# IoT_Indoor_Climate_Sensor-_upgraded.net
KiCad netlist of a schematic drawn in EasyEDA
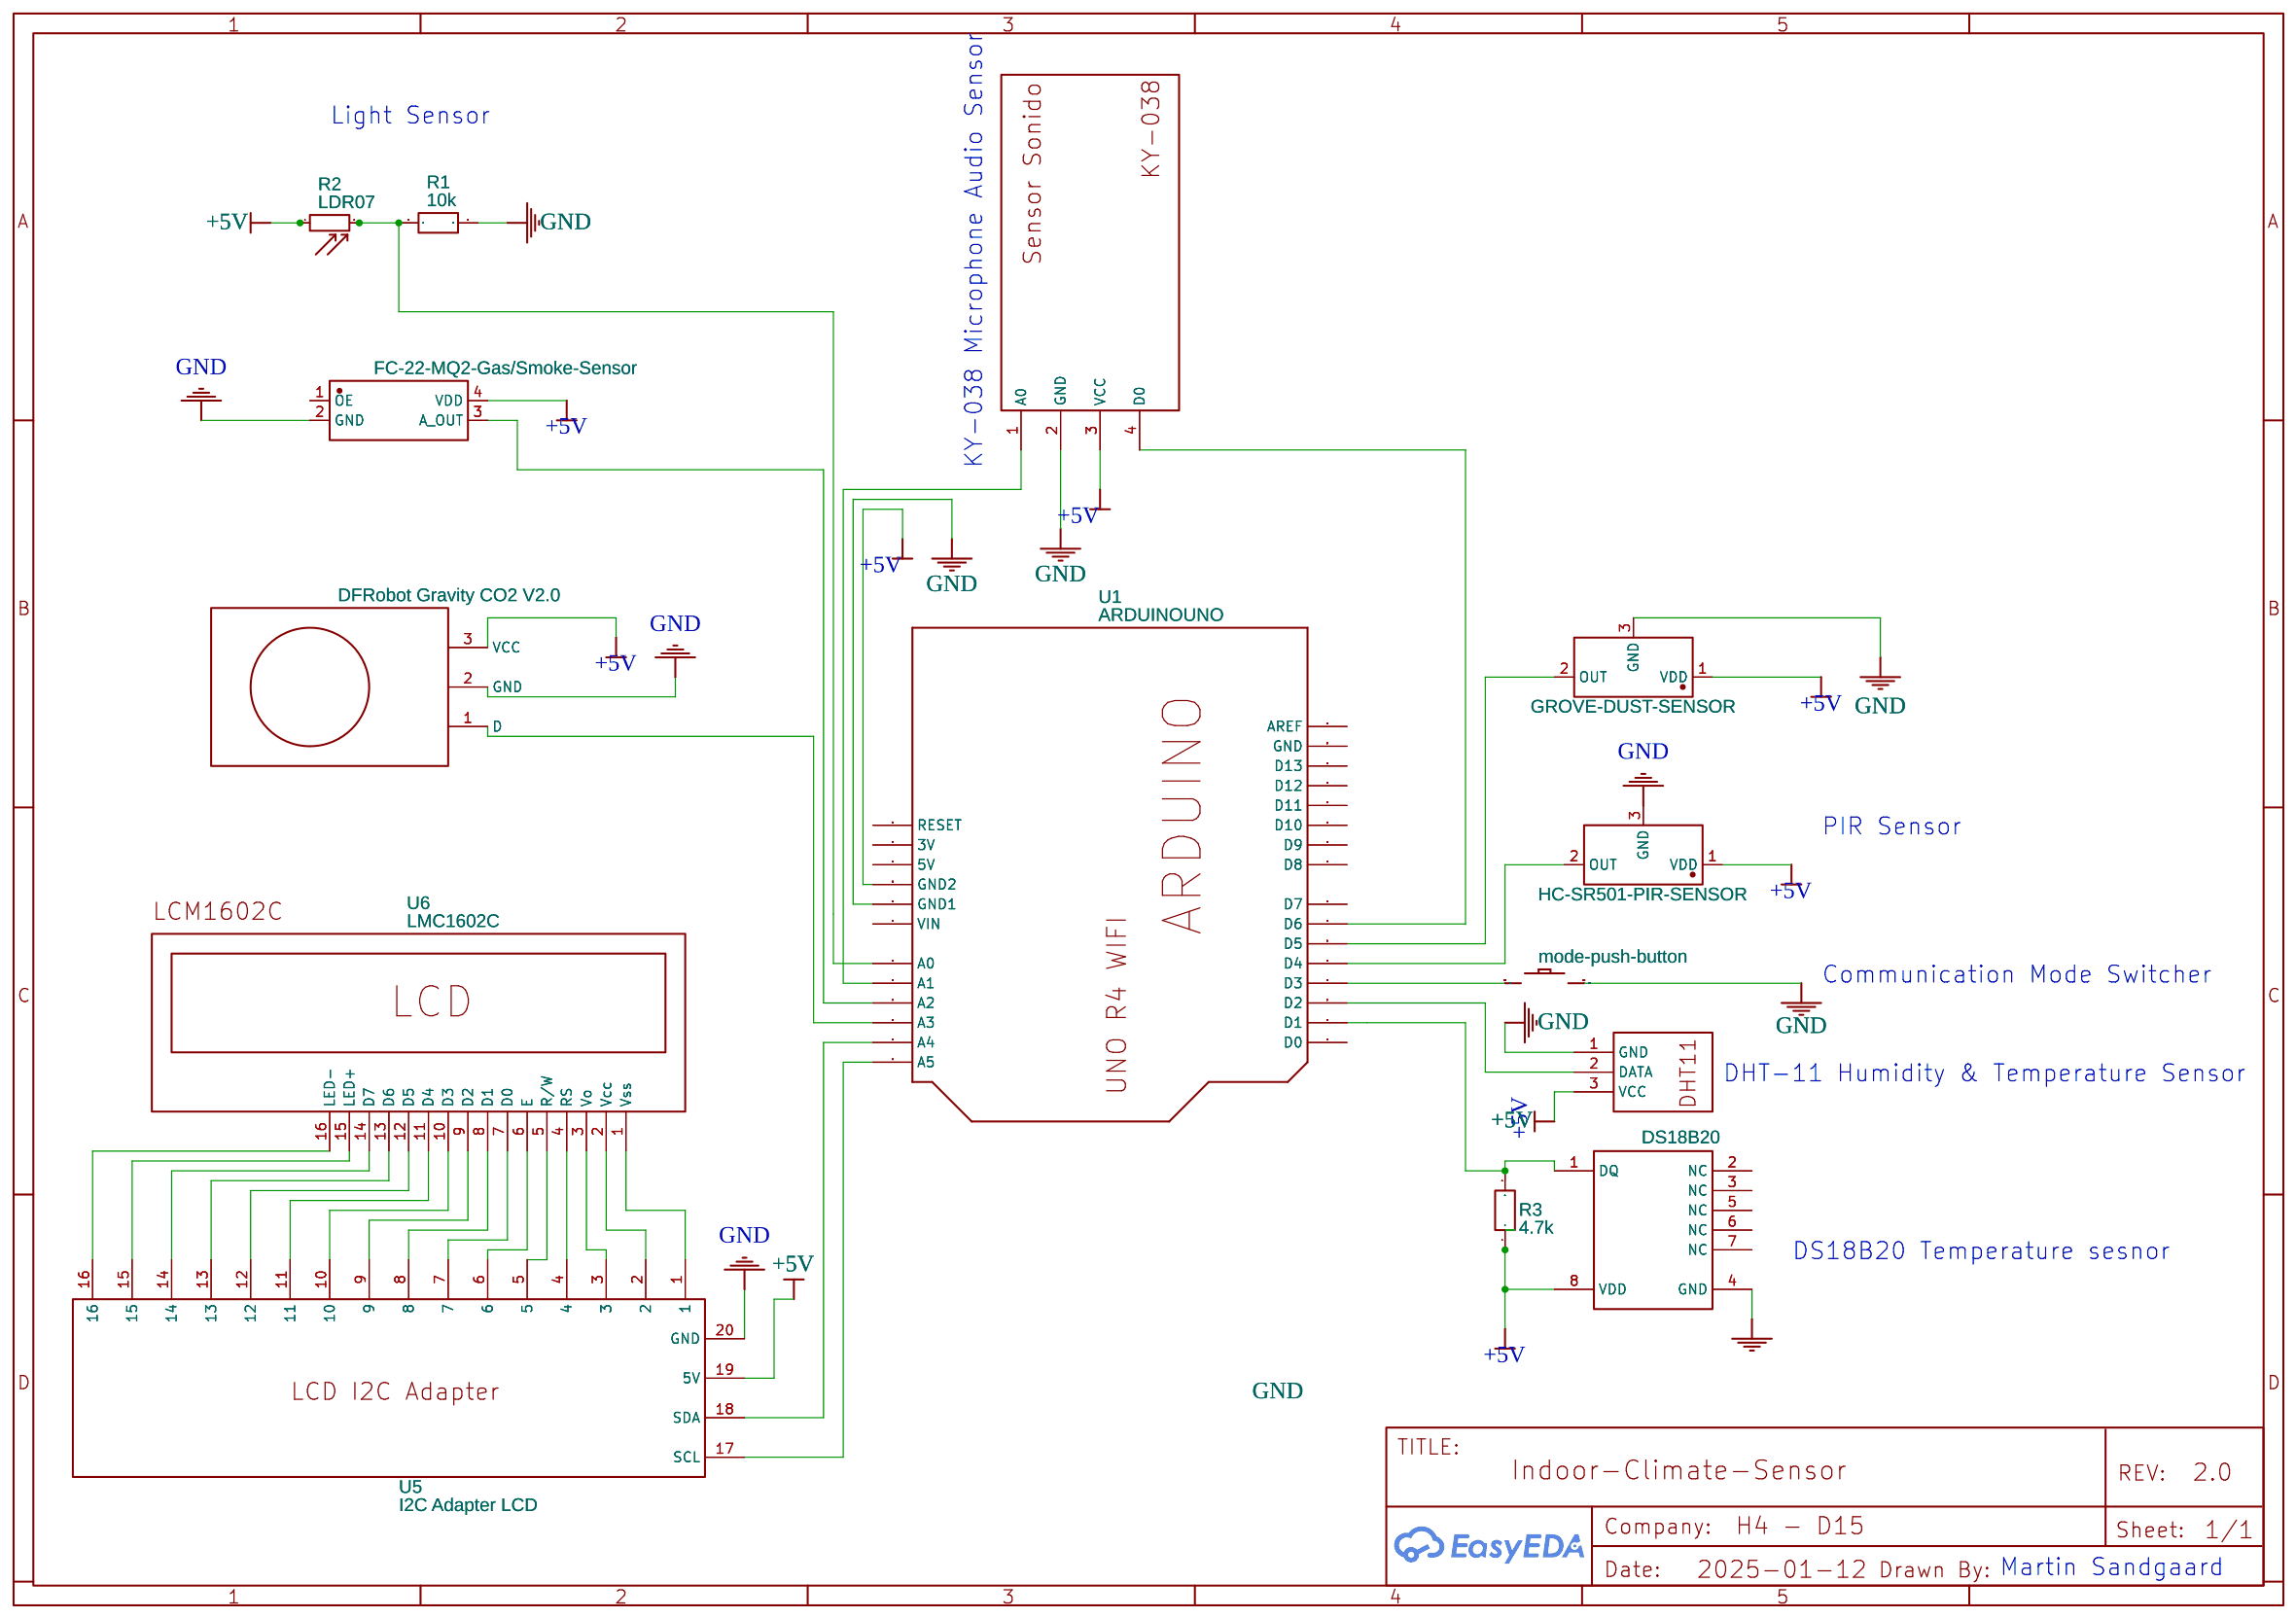
[diagram p0: schematic sheet]

(export (version "E")
  (design (tool "Eeschema 10.0.6"))
  (components
    (comp (ref "1") (value "mode-push-button") (libsource (lib "") (part "button")))
    (comp (ref "GROVE-DUST-SENSOR")
      (value "EKMB1309113K")
      (fields (field (name "Manufacturer") "PANASONIC(松下)"))
      (libsource (lib "") (part "EKMB1309113K"))
    )
    (comp (ref "HC-SR501-PIR-SENSOR")
      (value "EKMB1309113K")
      (fields (field (name "Manufacturer") "PANASONIC(松下)"))
      (libsource (lib "") (part "EKMB1309113K_1"))
    )
    (comp (ref "OSC1")
      (value "FC-22-MQ2-Gas/Smoke-Sensor")
      (fields (field (name "Manufacturer Part") "AMPMDFC-22.0000T3") (field (name "Manufacturer") "ABRACON"))
      (libsource (lib "") (part "AMPMDFC-22.0000T3"))
    )
    (comp (ref "R1") (value "10k") (libsource (lib "") (part "R_0603_EU_1")))
    (comp (ref "R2") (value "LDR07") (libsource (lib "") (part "LDR07")))
    (comp (ref "R3") (value "4.7k") (libsource (lib "") (part "R_0603_EU")))
    (comp (ref "U1") (value "ARDUINOUNO") (libsource (lib "") (part "ARDUINOUNO")))
    (comp (ref "U2") (value "DS18B20") (libsource (lib "") (part "DS18B20U+")))
    (comp (ref "U3")
      (value "KY-038 Microphone Sound Sensor")
      (libsource (lib "") (part "KY-037 KY038 SENSOR SONIDO COPY"))
    )
    (comp (ref "U4") (value "DHT-11") (libsource (lib "") (part "DHT-11")))
    (comp (ref "U5") (value "I2C Adapter LCD") (libsource (lib "") (part "I2C Adapter LCD")))
    (comp (ref "U6") (value "LMC1602C") (libsource (lib "") (part "LMC1602C")))
    (comp (ref "U7")
      (value "DFRobot Gravity CO2 V2.0")
      (libsource (lib "") (part "DFRobot Gravity - czujnik dwutlenku węgla CO2 - elektrochemiczny"))
    )
  )
  (nets
    (net (code "1") (name "+5V") (class "Default")
      (node (ref "GROVE-DUST-SENSOR") (pin "1") (pinfunction "VDD_1") (pintype "unspecified"))
      (node (ref "HC-SR501-PIR-SENSOR") (pin "1") (pinfunction "VDD_1") (pintype "unspecified"))
      (node (ref "OSC1") (pin "4") (pinfunction "VDD_4") (pintype "unspecified"))
      (node (ref "R2") (pin "1") (pintype "unspecified"))
      (node (ref "R3") (pin "1") (pinfunction "1_1") (pintype "unspecified"))
      (node (ref "U1") (pin "GND2") (pinfunction "GND2_GND2") (pintype "passive"))
      (node (ref "U2") (pin "8") (pinfunction "VDD_8") (pintype "passive"))
      (node (ref "U3") (pin "3") (pinfunction "VCC_3") (pintype "unspecified"))
      (node (ref "U4") (pin "3") (pinfunction "VCC_3") (pintype "unspecified"))
      (node (ref "U5") (pin "19") (pinfunction "5V_19") (pintype "unspecified"))
    )
    (net (code "2") (name "GND") (class "Default")
      (node (ref "1") (pin "P$ACTIVE") (pinfunction "P$ACTIVE_P$ACTIVE") (pintype "unspecified"))
      (node (ref "GROVE-DUST-SENSOR") (pin "3") (pinfunction "GND_3") (pintype "unspecified"))
      (node (ref "HC-SR501-PIR-SENSOR") (pin "3") (pinfunction "GND_3") (pintype "unspecified"))
      (node (ref "OSC1") (pin "2") (pinfunction "GND_2") (pintype "unspecified"))
      (node (ref "R1") (pin "1") (pinfunction "1_1") (pintype "unspecified"))
      (node (ref "U1") (pin "GND1") (pinfunction "GND1_GND1") (pintype "passive"))
      (node (ref "U2") (pin "4") (pinfunction "GND_4") (pintype "passive"))
      (node (ref "U3") (pin "2") (pinfunction "GND_2") (pintype "unspecified"))
      (node (ref "U4") (pin "1") (pinfunction "GND_1") (pintype "unspecified"))
      (node (ref "U5") (pin "20") (pinfunction "GND_20") (pintype "unspecified"))
    )
    (net (code "3") (name "Net-(1-PadP$GND)") (class "Default")
      (node (ref "1") (pin "P$GND") (pinfunction "P$GND_P$GND") (pintype "unspecified"))
      (node (ref "U1") (pin "D3") (pinfunction "D3_D3") (pintype "unspecified"))
    )
    (net (code "4") (name "Net-(GROVE-DUST-SENSOR-OUT)") (class "Default")
      (node (ref "GROVE-DUST-SENSOR") (pin "2") (pinfunction "OUT_2") (pintype "unspecified"))
      (node (ref "U1") (pin "D5") (pinfunction "D5_D5") (pintype "unspecified"))
    )
    (net (code "5") (name "Net-(HC-SR501-PIR-SENSOR-OUT)") (class "Default")
      (node (ref "HC-SR501-PIR-SENSOR") (pin "2") (pinfunction "OUT_2") (pintype "unspecified"))
      (node (ref "U1") (pin "D4") (pinfunction "D4_D4") (pintype "unspecified"))
    )
    (net (code "6") (name "Net-(OSC1-A_OUT)") (class "Default")
      (node (ref "OSC1") (pin "3") (pinfunction "A_OUT_3") (pintype "unspecified"))
      (node (ref "U1") (pin "A2") (pinfunction "A2_A2") (pintype "unspecified"))
    )
    (net (code "7") (name "Net-(R1-Pad2)") (class "Default")
      (node (ref "R1") (pin "2") (pinfunction "2_2") (pintype "unspecified"))
      (node (ref "R2") (pin "2") (pintype "unspecified"))
      (node (ref "U1") (pin "A0") (pinfunction "A0_A0") (pintype "unspecified"))
    )
    (net (code "8") (name "Net-(U2-DQ)") (class "Default")
      (node (ref "R3") (pin "2") (pinfunction "2_2") (pintype "unspecified"))
      (node (ref "U1") (pin "D1") (pinfunction "D1_D1") (pintype "unspecified"))
      (node (ref "U2") (pin "1") (pinfunction "DQ_1") (pintype "bidirectional"))
    )
    (net (code "9") (name "Net-(U3-A0)") (class "Default")
      (node (ref "U1") (pin "A1") (pinfunction "A1_A1") (pintype "unspecified"))
      (node (ref "U3") (pin "1") (pinfunction "A0_1") (pintype "unspecified"))
    )
    (net (code "10") (name "Net-(U3-D0)") (class "Default")
      (node (ref "U1") (pin "D6") (pinfunction "D6_D6") (pintype "unspecified"))
      (node (ref "U3") (pin "4") (pinfunction "D0_4") (pintype "unspecified"))
    )
    (net (code "11") (name "Net-(U4-DATA)") (class "Default")
      (node (ref "U1") (pin "D2") (pinfunction "D2_D2") (pintype "unspecified"))
      (node (ref "U4") (pin "2") (pinfunction "DATA_2") (pintype "unspecified"))
    )
    (net (code "12") (name "Net-(U5-SCL)") (class "Default")
      (node (ref "U1") (pin "A5") (pinfunction "A5_A5") (pintype "unspecified"))
      (node (ref "U5") (pin "17") (pinfunction "SCL_17") (pintype "unspecified"))
    )
    (net (code "13") (name "Net-(U5-SDA)") (class "Default")
      (node (ref "U1") (pin "A4") (pinfunction "A4_A4") (pintype "unspecified"))
      (node (ref "U5") (pin "18") (pinfunction "SDA_18") (pintype "unspecified"))
    )
    (net (code "14") (name "Net-(U6-D0)") (class "Default")
      (node (ref "U5") (pin "7") (pinfunction "7_7") (pintype "unspecified"))
      (node (ref "U6") (pin "7") (pinfunction "D0_7") (pintype "unspecified"))
    )
    (net (code "15") (name "Net-(U6-D1)") (class "Default")
      (node (ref "U5") (pin "8") (pinfunction "8_8") (pintype "unspecified"))
      (node (ref "U6") (pin "8") (pinfunction "D1_8") (pintype "unspecified"))
    )
    (net (code "16") (name "Net-(U6-D2)") (class "Default")
      (node (ref "U5") (pin "9") (pinfunction "9_9") (pintype "unspecified"))
      (node (ref "U6") (pin "9") (pinfunction "D2_9") (pintype "unspecified"))
    )
    (net (code "17") (name "Net-(U6-D3)") (class "Default")
      (node (ref "U5") (pin "10") (pinfunction "10_10") (pintype "unspecified"))
      (node (ref "U6") (pin "10") (pinfunction "D3_10") (pintype "unspecified"))
    )
    (net (code "18") (name "Net-(U6-D4)") (class "Default")
      (node (ref "U5") (pin "11") (pinfunction "11_11") (pintype "unspecified"))
      (node (ref "U6") (pin "11") (pinfunction "D4_11") (pintype "unspecified"))
    )
    (net (code "19") (name "Net-(U6-D5)") (class "Default")
      (node (ref "U5") (pin "12") (pinfunction "12_12") (pintype "unspecified"))
      (node (ref "U6") (pin "12") (pinfunction "D5_12") (pintype "unspecified"))
    )
    (net (code "20") (name "Net-(U6-D6)") (class "Default")
      (node (ref "U5") (pin "13") (pinfunction "13_13") (pintype "unspecified"))
      (node (ref "U6") (pin "13") (pinfunction "D6_13") (pintype "unspecified"))
    )
    (net (code "21") (name "Net-(U6-D7)") (class "Default")
      (node (ref "U5") (pin "14") (pinfunction "14_14") (pintype "unspecified"))
      (node (ref "U6") (pin "14") (pinfunction "D7_14") (pintype "unspecified"))
    )
    (net (code "22") (name "Net-(U6-E)") (class "Default")
      (node (ref "U5") (pin "6") (pinfunction "6_6") (pintype "unspecified"))
      (node (ref "U6") (pin "6") (pinfunction "E_6") (pintype "unspecified"))
    )
    (net (code "23") (name "Net-(U6-LED+)") (class "Default")
      (node (ref "U5") (pin "15") (pinfunction "15_15") (pintype "unspecified"))
      (node (ref "U6") (pin "15") (pinfunction "LED+_15") (pintype "unspecified"))
    )
    (net (code "24") (name "Net-(U6-LED-)") (class "Default")
      (node (ref "U5") (pin "16") (pinfunction "16_16") (pintype "unspecified"))
      (node (ref "U6") (pin "16") (pinfunction "LED-_16") (pintype "unspecified"))
    )
    (net (code "25") (name "Net-(U6-RS)") (class "Default")
      (node (ref "U5") (pin "4") (pinfunction "4_4") (pintype "unspecified"))
      (node (ref "U6") (pin "4") (pinfunction "RS_4") (pintype "unspecified"))
    )
    (net (code "26") (name "Net-(U6-R{slash}W)") (class "Default")
      (node (ref "U5") (pin "5") (pinfunction "5_5") (pintype "unspecified"))
      (node (ref "U6") (pin "5") (pinfunction "R/W_5") (pintype "unspecified"))
    )
    (net (code "27") (name "Net-(U6-Vcc)") (class "Default")
      (node (ref "U5") (pin "2") (pinfunction "2_2") (pintype "unspecified"))
      (node (ref "U6") (pin "2") (pinfunction "Vcc_2") (pintype "unspecified"))
    )
    (net (code "28") (name "Net-(U6-Vo)") (class "Default")
      (node (ref "U5") (pin "3") (pinfunction "3_3") (pintype "unspecified"))
      (node (ref "U6") (pin "3") (pinfunction "Vo_3") (pintype "unspecified"))
    )
    (net (code "29") (name "Net-(U6-Vss)") (class "Default")
      (node (ref "U5") (pin "1") (pinfunction "1_1") (pintype "unspecified"))
      (node (ref "U6") (pin "1") (pinfunction "Vss_1") (pintype "unspecified"))
    )
    (net (code "30") (name "unconnected-(OSC1-OE-Pad1)") (class "Default")
      (node (ref "OSC1") (pin "1") (pinfunction "OE_1") (pintype "unspecified"))
    )
    (net (code "31") (name "unconnected-(U1-Pad3V)") (class "Default")
      (node (ref "U1") (pin "3V") (pinfunction "3V_3V") (pintype "passive"))
    )
    (net (code "32") (name "unconnected-(U1-Pad5V)") (class "Default")
      (node (ref "U1") (pin "5V") (pinfunction "5V_5V") (pintype "passive"))
    )
    (net (code "33") (name "unconnected-(U1-PadA3)") (class "Default")
      (node (ref "U1") (pin "A3") (pinfunction "A3_A3") (pintype "unspecified"))
    )
    (net (code "34") (name "unconnected-(U1-PadAREF)") (class "Default")
      (node (ref "U1") (pin "AREF") (pinfunction "AREF_AREF") (pintype "unspecified"))
    )
    (net (code "35") (name "unconnected-(U1-PadD0)") (class "Default")
      (node (ref "U1") (pin "D0") (pinfunction "D0_D0") (pintype "unspecified"))
    )
    (net (code "36") (name "unconnected-(U1-PadD7)") (class "Default")
      (node (ref "U1") (pin "D7") (pinfunction "D7_D7") (pintype "unspecified"))
    )
    (net (code "37") (name "unconnected-(U1-PadD8)") (class "Default")
      (node (ref "U1") (pin "D8") (pinfunction "D8_D8") (pintype "unspecified"))
    )
    (net (code "38") (name "unconnected-(U1-PadD9)") (class "Default")
      (node (ref "U1") (pin "D9") (pinfunction "D9_D9") (pintype "unspecified"))
    )
    (net (code "39") (name "unconnected-(U1-PadD10)") (class "Default")
      (node (ref "U1") (pin "D10") (pinfunction "D10_D10") (pintype "unspecified"))
    )
    (net (code "40") (name "unconnected-(U1-PadD11)") (class "Default")
      (node (ref "U1") (pin "D11") (pinfunction "D11_D11") (pintype "unspecified"))
    )
    (net (code "41") (name "unconnected-(U1-PadD12)") (class "Default")
      (node (ref "U1") (pin "D12") (pinfunction "D12_D12") (pintype "unspecified"))
    )
    (net (code "42") (name "unconnected-(U1-PadD13)") (class "Default")
      (node (ref "U1") (pin "D13") (pinfunction "D13_D13") (pintype "unspecified"))
    )
    (net (code "43") (name "unconnected-(U1-PadGND)") (class "Default")
      (node (ref "U1") (pin "GND") (pinfunction "GND_GND") (pintype "passive"))
    )
    (net (code "44") (name "unconnected-(U1-PadRESET)") (class "Default")
      (node (ref "U1") (pin "RESET") (pinfunction "RESET_RESET") (pintype "unspecified"))
    )
    (net (code "45") (name "unconnected-(U1-PadVIN)") (class "Default")
      (node (ref "U1") (pin "VIN") (pinfunction "VIN_VIN") (pintype "passive"))
    )
    (net (code "46") (name "unconnected-(U2-NC-Pad2)") (class "Default")
      (node (ref "U2") (pin "2") (pinfunction "NC_2") (pintype "unspecified"))
    )
    (net (code "47") (name "unconnected-(U2-NC-Pad3)") (class "Default")
      (node (ref "U2") (pin "3") (pinfunction "NC_3") (pintype "unspecified"))
    )
    (net (code "48") (name "unconnected-(U2-NC-Pad5)") (class "Default")
      (node (ref "U2") (pin "5") (pinfunction "NC_5") (pintype "unspecified"))
    )
    (net (code "49") (name "unconnected-(U2-NC-Pad6)") (class "Default")
      (node (ref "U2") (pin "6") (pinfunction "NC_6") (pintype "unspecified"))
    )
    (net (code "50") (name "unconnected-(U2-NC-Pad7)") (class "Default")
      (node (ref "U2") (pin "7") (pinfunction "NC_7") (pintype "unspecified"))
    )
    (net (code "51") (name "unconnected-(U7-D-Pad1)") (class "Default")
      (node (ref "U7") (pin "1") (pinfunction "D_1") (pintype "unspecified"))
    )
    (net (code "52") (name "unconnected-(U7-GND-Pad2)") (class "Default")
      (node (ref "U7") (pin "2") (pinfunction "GND_2") (pintype "unspecified"))
    )
    (net (code "53") (name "unconnected-(U7-VCC-Pad3)") (class "Default")
      (node (ref "U7") (pin "3") (pinfunction "VCC_3") (pintype "unspecified"))
    )
  )
)
